# Ethernet.net
KiCad netlist of a schematic drawn in Altium Designer
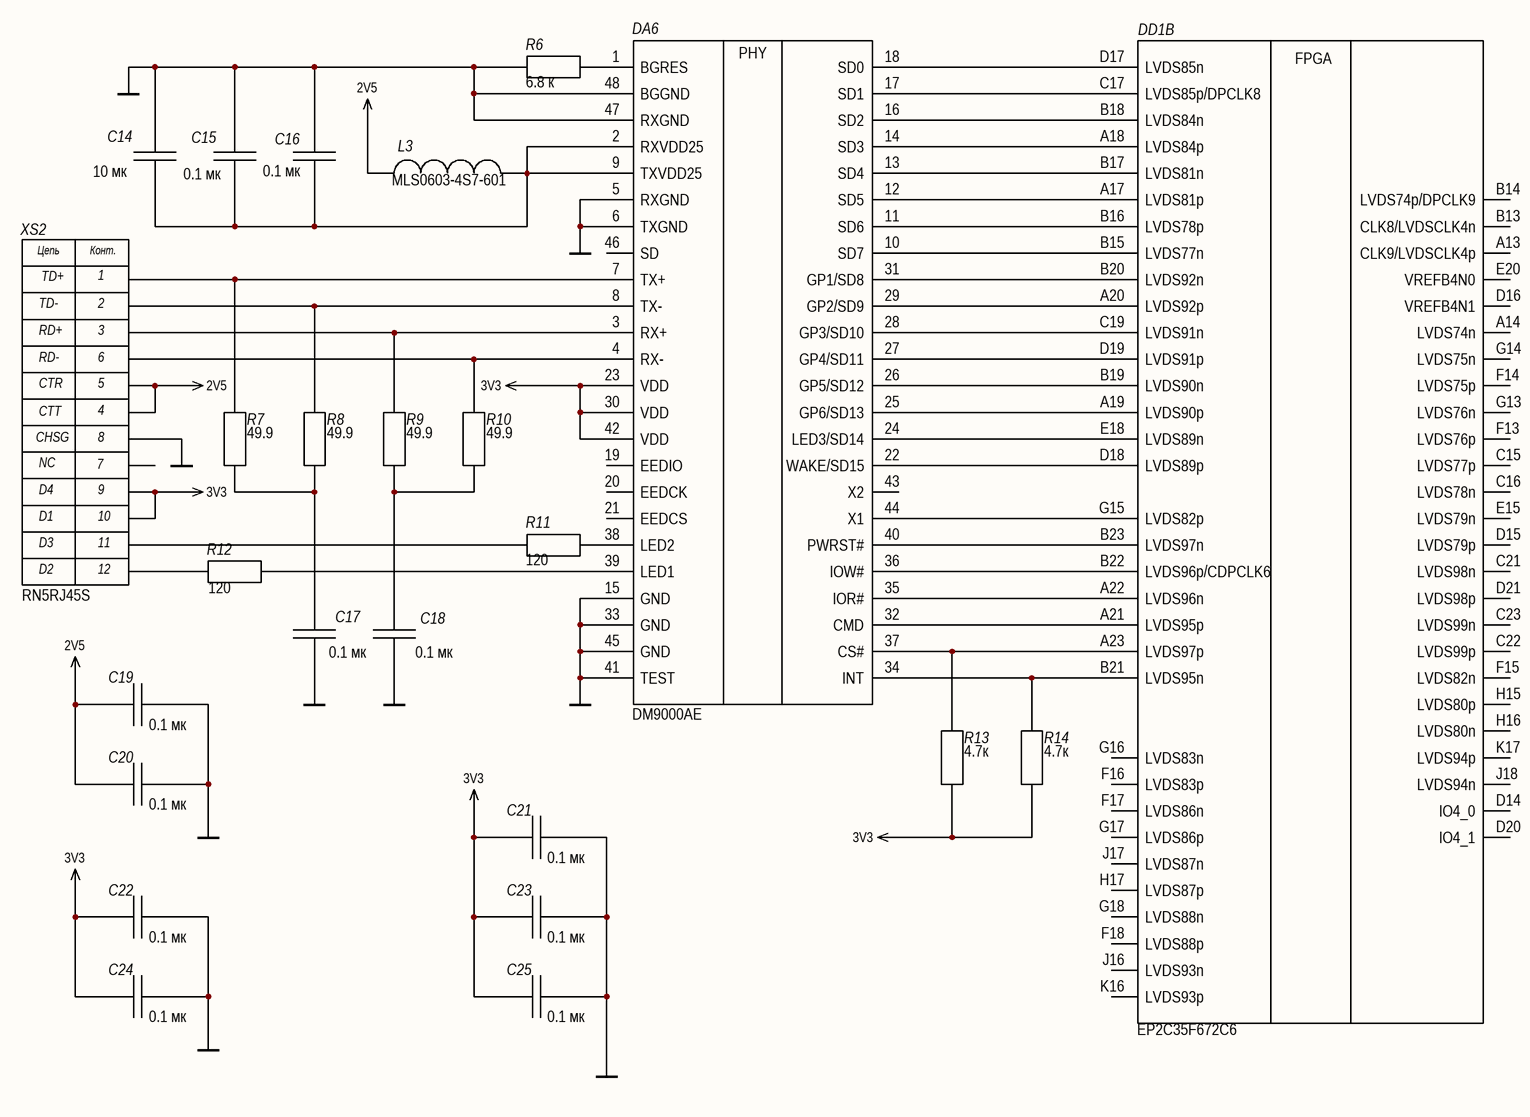
[diagram p0: Ethernet.SchDoc]

(export (version "E")
  (design (tool "Eeschema 10.0.6"))
  (components
    (comp (ref "C14") (value "~") (libsource (lib "Schlib1") (part "C")))
    (comp (ref "C15") (value "~") (libsource (lib "Schlib1") (part "C")))
    (comp (ref "C16") (value "~") (libsource (lib "Schlib1") (part "C")))
    (comp (ref "C17") (value "~") (libsource (lib "Schlib1") (part "C")))
    (comp (ref "C18") (value "~") (libsource (lib "Schlib1") (part "C")))
    (comp (ref "C19") (value "~") (libsource (lib "Schlib1") (part "C")))
    (comp (ref "C20") (value "~") (libsource (lib "Schlib1") (part "C")))
    (comp (ref "C21") (value "~") (libsource (lib "Schlib1") (part "C")))
    (comp (ref "C22") (value "~") (libsource (lib "Schlib1") (part "C")))
    (comp (ref "C23") (value "~") (libsource (lib "Schlib1") (part "C")))
    (comp (ref "C24") (value "~") (libsource (lib "Schlib1") (part "C")))
    (comp (ref "C25") (value "~") (libsource (lib "Schlib1") (part "C")))
    (comp (ref "DA6") (value "DM9000AE") (libsource (lib "Schlib1") (part "DM9000AE")))
    (comp (ref "DD1") (value "EP2C35F672C6") (libsource (lib "Schlib1") (part "PLIS")))
    (comp (ref "L3") (value "L") (libsource (lib "Schlib1") (part "L")))
    (comp (ref "R6") (value "6.8 к") (libsource (lib "Schlib1") (part "R")))
    (comp (ref "R7") (value "49.9") (libsource (lib "Schlib1") (part "R")))
    (comp (ref "R8") (value "49.9") (libsource (lib "Schlib1") (part "R")))
    (comp (ref "R9") (value "49.9") (libsource (lib "Schlib1") (part "R")))
    (comp (ref "R10") (value "49.9") (libsource (lib "Schlib1") (part "R")))
    (comp (ref "R11") (value "120") (libsource (lib "Schlib1") (part "R")))
    (comp (ref "R12") (value "120") (libsource (lib "Schlib1") (part "R")))
    (comp (ref "R13") (value "4.7к") (libsource (lib "Schlib1") (part "R")))
    (comp (ref "R14") (value "4.7к") (libsource (lib "Schlib1") (part "R")))
    (comp (ref "XS2") (value "RN5RJ45S") (libsource (lib "Schlib1") (part "Ethernet_RJ45")))
  )
  (nets
    (net (code "1") (name "2V5") (class "Default")
      (node (ref "C19") (pin "2") (pintype "passive"))
      (node (ref "C20") (pin "2") (pintype "passive"))
      (node (ref "L3") (pin "1") (pinfunction "1_1") (pintype "passive"))
      (node (ref "XS2") (pin "4") (pinfunction "4_4") (pintype "passive"))
      (node (ref "XS2") (pin "5") (pinfunction "5_5") (pintype "passive"))
    )
    (net (code "2") (name "3V3") (class "Default")
      (node (ref "C21") (pin "2") (pintype "passive"))
      (node (ref "C22") (pin "2") (pintype "passive"))
      (node (ref "C23") (pin "2") (pintype "passive"))
      (node (ref "C24") (pin "2") (pintype "passive"))
      (node (ref "C25") (pin "2") (pintype "passive"))
      (node (ref "DA6") (pin "23") (pinfunction "VDD_23") (pintype "passive"))
      (node (ref "DA6") (pin "30") (pinfunction "VDD_30") (pintype "passive"))
      (node (ref "DA6") (pin "42") (pinfunction "VDD_42") (pintype "passive"))
      (node (ref "R13") (pin "1") (pinfunction "1_1") (pintype "passive"))
      (node (ref "R14") (pin "1") (pinfunction "1_1") (pintype "passive"))
      (node (ref "XS2") (pin "10") (pinfunction "10_10") (pintype "passive"))
      (node (ref "XS2") (pin "9") (pinfunction "9_9") (pintype "passive"))
    )
    (net (code "3") (name "GND") (class "Default")
      (node (ref "C14") (pin "2") (pintype "passive"))
      (node (ref "C15") (pin "2") (pintype "passive"))
      (node (ref "C16") (pin "2") (pintype "passive"))
      (node (ref "C17") (pin "1") (pintype "passive"))
      (node (ref "C18") (pin "1") (pintype "passive"))
      (node (ref "C19") (pin "1") (pintype "passive"))
      (node (ref "C20") (pin "1") (pintype "passive"))
      (node (ref "C21") (pin "1") (pintype "passive"))
      (node (ref "C22") (pin "1") (pintype "passive"))
      (node (ref "C23") (pin "1") (pintype "passive"))
      (node (ref "C24") (pin "1") (pintype "passive"))
      (node (ref "C25") (pin "1") (pintype "passive"))
      (node (ref "DA6") (pin "15") (pinfunction "GND_15") (pintype "passive"))
      (node (ref "DA6") (pin "33") (pinfunction "GND_33") (pintype "passive"))
      (node (ref "DA6") (pin "41") (pinfunction "TEST_41") (pintype "passive"))
      (node (ref "DA6") (pin "45") (pinfunction "GND_45") (pintype "passive"))
      (node (ref "DA6") (pin "47") (pinfunction "RXGND_47") (pintype "passive"))
      (node (ref "DA6") (pin "48") (pinfunction "BGGND_48") (pintype "passive"))
      (node (ref "DA6") (pin "5") (pinfunction "RXGND_5") (pintype "passive"))
      (node (ref "DA6") (pin "6") (pinfunction "TXGND_6") (pintype "passive"))
      (node (ref "R6") (pin "1") (pinfunction "1_1") (pintype "passive"))
      (node (ref "XS2") (pin "8") (pinfunction "8_8") (pintype "passive"))
    )
    (net (code "4") (name "Net-(C17-Pad2)") (class "Default")
      (node (ref "C17") (pin "2") (pintype "passive"))
      (node (ref "R7") (pin "1") (pinfunction "1_1") (pintype "passive"))
      (node (ref "R8") (pin "1") (pinfunction "1_1") (pintype "passive"))
    )
    (net (code "5") (name "Net-(C18-Pad2)") (class "Default")
      (node (ref "C18") (pin "2") (pintype "passive"))
      (node (ref "R10") (pin "1") (pinfunction "1_1") (pintype "passive"))
      (node (ref "R9") (pin "1") (pinfunction "1_1") (pintype "passive"))
    )
    (net (code "6") (name "Net-(DA6-BGRES)") (class "Default")
      (node (ref "DA6") (pin "1") (pinfunction "BGRES_1") (pintype "passive"))
      (node (ref "R6") (pin "2") (pinfunction "2_2") (pintype "passive"))
    )
    (net (code "7") (name "Net-(DA6-CMD)") (class "Default")
      (node (ref "DA6") (pin "32") (pinfunction "CMD_32") (pintype "passive"))
      (node (ref "DD1") (pin "A21") (pinfunction "LVDS95p_A21") (pintype "passive"))
    )
    (net (code "8") (name "Net-(DA6-CS#)") (class "Default")
      (node (ref "DA6") (pin "37") (pinfunction "CS#_37") (pintype "passive"))
      (node (ref "DD1") (pin "A23") (pinfunction "LVDS97p_A23") (pintype "passive"))
      (node (ref "R13") (pin "2") (pinfunction "2_2") (pintype "passive"))
    )
    (net (code "9") (name "Net-(DA6-GP1{slash}SD8)") (class "Default")
      (node (ref "DA6") (pin "31") (pinfunction "GP1/SD8_31") (pintype "passive"))
      (node (ref "DD1") (pin "B20") (pinfunction "LVDS92n_B20") (pintype "passive"))
    )
    (net (code "10") (name "Net-(DA6-GP2{slash}SD9)") (class "Default")
      (node (ref "DA6") (pin "29") (pinfunction "GP2/SD9_29") (pintype "passive"))
      (node (ref "DD1") (pin "A20") (pinfunction "LVDS92p_A20") (pintype "passive"))
    )
    (net (code "11") (name "Net-(DA6-GP3{slash}SD10)") (class "Default")
      (node (ref "DA6") (pin "28") (pinfunction "GP3/SD10_28") (pintype "passive"))
      (node (ref "DD1") (pin "C19") (pinfunction "LVDS91n_C19") (pintype "passive"))
    )
    (net (code "12") (name "Net-(DA6-GP4{slash}SD11)") (class "Default")
      (node (ref "DA6") (pin "27") (pinfunction "GP4/SD11_27") (pintype "passive"))
      (node (ref "DD1") (pin "D19") (pinfunction "LVDS91p_D19") (pintype "passive"))
    )
    (net (code "13") (name "Net-(DA6-GP5{slash}SD12)") (class "Default")
      (node (ref "DA6") (pin "26") (pinfunction "GP5/SD12_26") (pintype "passive"))
      (node (ref "DD1") (pin "B19") (pinfunction "LVDS90n_B19") (pintype "passive"))
    )
    (net (code "14") (name "Net-(DA6-GP6{slash}SD13)") (class "Default")
      (node (ref "DA6") (pin "25") (pinfunction "GP6/SD13_25") (pintype "passive"))
      (node (ref "DD1") (pin "A19") (pinfunction "LVDS90p_A19") (pintype "passive"))
    )
    (net (code "15") (name "Net-(DA6-INT)") (class "Default")
      (node (ref "DA6") (pin "34") (pinfunction "INT_34") (pintype "passive"))
      (node (ref "DD1") (pin "B21") (pinfunction "LVDS95n_B21") (pintype "passive"))
      (node (ref "R14") (pin "2") (pinfunction "2_2") (pintype "passive"))
    )
    (net (code "16") (name "Net-(DA6-IOR#)") (class "Default")
      (node (ref "DA6") (pin "35") (pinfunction "IOR#_35") (pintype "passive"))
      (node (ref "DD1") (pin "A22") (pinfunction "LVDS96n_A22") (pintype "passive"))
    )
    (net (code "17") (name "Net-(DA6-IOW#)") (class "Default")
      (node (ref "DA6") (pin "36") (pinfunction "IOW#_36") (pintype "passive"))
      (node (ref "DD1") (pin "B22") (pinfunction "LVDS96p/CDPCLK6_B22") (pintype "passive"))
    )
    (net (code "18") (name "Net-(DA6-LED1)") (class "Default")
      (node (ref "DA6") (pin "39") (pinfunction "LED1_39") (pintype "passive"))
      (node (ref "R12") (pin "2") (pinfunction "2_2") (pintype "passive"))
    )
    (net (code "19") (name "Net-(DA6-LED2)") (class "Default")
      (node (ref "DA6") (pin "38") (pinfunction "LED2_38") (pintype "passive"))
      (node (ref "R11") (pin "2") (pinfunction "2_2") (pintype "passive"))
    )
    (net (code "20") (name "Net-(DA6-LED3{slash}SD14)") (class "Default")
      (node (ref "DA6") (pin "24") (pinfunction "LED3/SD14_24") (pintype "passive"))
      (node (ref "DD1") (pin "E18") (pinfunction "LVDS89n_E18") (pintype "passive"))
    )
    (net (code "21") (name "Net-(DA6-PWRST#)") (class "Default")
      (node (ref "DA6") (pin "40") (pinfunction "PWRST#_40") (pintype "passive"))
      (node (ref "DD1") (pin "B23") (pinfunction "LVDS97n_B23") (pintype "passive"))
    )
    (net (code "22") (name "Net-(DA6-RX+)") (class "Default")
      (node (ref "DA6") (pin "3") (pinfunction "RX+_3") (pintype "passive"))
      (node (ref "R9") (pin "2") (pinfunction "2_2") (pintype "passive"))
      (node (ref "XS2") (pin "3") (pinfunction "3_3") (pintype "passive"))
    )
    (net (code "23") (name "Net-(DA6-RX-)") (class "Default")
      (node (ref "DA6") (pin "4") (pinfunction "RX-_4") (pintype "passive"))
      (node (ref "R10") (pin "2") (pinfunction "2_2") (pintype "passive"))
      (node (ref "XS2") (pin "6") (pinfunction "6_6") (pintype "passive"))
    )
    (net (code "24") (name "Net-(DA6-RXVDD25)") (class "Default")
      (node (ref "C14") (pin "1") (pintype "passive"))
      (node (ref "C15") (pin "1") (pintype "passive"))
      (node (ref "C16") (pin "1") (pintype "passive"))
      (node (ref "DA6") (pin "2") (pinfunction "RXVDD25_2") (pintype "passive"))
      (node (ref "DA6") (pin "9") (pinfunction "TXVDD25_9") (pintype "passive"))
      (node (ref "L3") (pin "2") (pinfunction "2_2") (pintype "passive"))
    )
    (net (code "25") (name "Net-(DA6-SD0)") (class "Default")
      (node (ref "DA6") (pin "18") (pinfunction "SD0_18") (pintype "passive"))
      (node (ref "DD1") (pin "D17") (pinfunction "LVDS85n_D17") (pintype "passive"))
    )
    (net (code "26") (name "Net-(DA6-SD1)") (class "Default")
      (node (ref "DA6") (pin "17") (pinfunction "SD1_17") (pintype "passive"))
      (node (ref "DD1") (pin "C17") (pinfunction "LVDS85p/DPCLK8_C17") (pintype "passive"))
    )
    (net (code "27") (name "Net-(DA6-SD2)") (class "Default")
      (node (ref "DA6") (pin "16") (pinfunction "SD2_16") (pintype "passive"))
      (node (ref "DD1") (pin "B18") (pinfunction "LVDS84n_B18") (pintype "passive"))
    )
    (net (code "28") (name "Net-(DA6-SD3)") (class "Default")
      (node (ref "DA6") (pin "14") (pinfunction "SD3_14") (pintype "passive"))
      (node (ref "DD1") (pin "A18") (pinfunction "LVDS84p_A18") (pintype "passive"))
    )
    (net (code "29") (name "Net-(DA6-SD4)") (class "Default")
      (node (ref "DA6") (pin "13") (pinfunction "SD4_13") (pintype "passive"))
      (node (ref "DD1") (pin "B17") (pinfunction "LVDS81n_B17") (pintype "passive"))
    )
    (net (code "30") (name "Net-(DA6-SD5)") (class "Default")
      (node (ref "DA6") (pin "12") (pinfunction "SD5_12") (pintype "passive"))
      (node (ref "DD1") (pin "A17") (pinfunction "LVDS81p_A17") (pintype "passive"))
    )
    (net (code "31") (name "Net-(DA6-SD6)") (class "Default")
      (node (ref "DA6") (pin "11") (pinfunction "SD6_11") (pintype "passive"))
      (node (ref "DD1") (pin "B16") (pinfunction "LVDS78p_B16") (pintype "passive"))
    )
    (net (code "32") (name "Net-(DA6-SD7)") (class "Default")
      (node (ref "DA6") (pin "10") (pinfunction "SD7_10") (pintype "passive"))
      (node (ref "DD1") (pin "B15") (pinfunction "LVDS77n_B15") (pintype "passive"))
    )
    (net (code "33") (name "Net-(DA6-TX+)") (class "Default")
      (node (ref "DA6") (pin "7") (pinfunction "TX+_7") (pintype "passive"))
      (node (ref "R7") (pin "2") (pinfunction "2_2") (pintype "passive"))
      (node (ref "XS2") (pin "1") (pinfunction "1_1") (pintype "passive"))
    )
    (net (code "34") (name "Net-(DA6-TX-)") (class "Default")
      (node (ref "DA6") (pin "8") (pinfunction "TX-_8") (pintype "passive"))
      (node (ref "R8") (pin "2") (pinfunction "2_2") (pintype "passive"))
      (node (ref "XS2") (pin "2") (pinfunction "2_2") (pintype "passive"))
    )
    (net (code "35") (name "Net-(DA6-WAKE{slash}SD15)") (class "Default")
      (node (ref "DA6") (pin "22") (pinfunction "WAKE/SD15_22") (pintype "passive"))
      (node (ref "DD1") (pin "D18") (pinfunction "LVDS89p_D18") (pintype "passive"))
    )
    (net (code "36") (name "Net-(DA6-X1)") (class "Default")
      (node (ref "DA6") (pin "44") (pinfunction "X1_44") (pintype "passive"))
      (node (ref "DD1") (pin "G15") (pinfunction "LVDS82p_G15") (pintype "passive"))
    )
    (net (code "37") (name "Net-(R11-Pad1)") (class "Default")
      (node (ref "R11") (pin "1") (pinfunction "1_1") (pintype "passive"))
      (node (ref "XS2") (pin "11") (pinfunction "11_11") (pintype "passive"))
    )
    (net (code "38") (name "Net-(R12-Pad1)") (class "Default")
      (node (ref "R12") (pin "1") (pinfunction "1_1") (pintype "passive"))
      (node (ref "XS2") (pin "12") (pinfunction "12_12") (pintype "passive"))
    )
    (net (code "39") (name "unconnected-(DA6-EEDCK-Pad20)") (class "Default")
      (node (ref "DA6") (pin "20") (pinfunction "EEDCK_20") (pintype "passive"))
    )
    (net (code "40") (name "unconnected-(DA6-EEDCS-Pad21)") (class "Default")
      (node (ref "DA6") (pin "21") (pinfunction "EEDCS_21") (pintype "passive"))
    )
    (net (code "41") (name "unconnected-(DA6-EEDIO-Pad19)") (class "Default")
      (node (ref "DA6") (pin "19") (pinfunction "EEDIO_19") (pintype "passive"))
    )
    (net (code "42") (name "unconnected-(DA6-SD-Pad46)") (class "Default")
      (node (ref "DA6") (pin "46") (pinfunction "SD_46") (pintype "passive"))
    )
    (net (code "43") (name "unconnected-(DA6-X2-Pad43)") (class "Default")
      (node (ref "DA6") (pin "43") (pinfunction "X2_43") (pintype "passive"))
    )
    (net (code "44") (name "unconnected-(DD1B-CLK8{slash}LVDSCLK4n-PadB13)") (class "Default")
      (node (ref "DD1") (pin "B13") (pinfunction "CLK8/LVDSCLK4n_B13") (pintype "passive"))
    )
    (net (code "45") (name "unconnected-(DD1B-CLK9{slash}LVDSCLK4p-PadA13)") (class "Default")
      (node (ref "DD1") (pin "A13") (pinfunction "CLK9/LVDSCLK4p_A13") (pintype "passive"))
    )
    (net (code "46") (name "unconnected-(DD1B-IO4_0-PadD14)") (class "Default")
      (node (ref "DD1") (pin "D14") (pinfunction "IO4_0_D14") (pintype "passive"))
    )
    (net (code "47") (name "unconnected-(DD1B-IO4_1-PadD20)") (class "Default")
      (node (ref "DD1") (pin "D20") (pinfunction "IO4_1_D20") (pintype "passive"))
    )
    (net (code "48") (name "unconnected-(DD1B-LVDS74n-PadA14)") (class "Default")
      (node (ref "DD1") (pin "A14") (pinfunction "LVDS74n_A14") (pintype "passive"))
    )
    (net (code "49") (name "unconnected-(DD1B-LVDS74p{slash}DPCLK9-PadB14)") (class "Default")
      (node (ref "DD1") (pin "B14") (pinfunction "LVDS74p/DPCLK9_B14") (pintype "passive"))
    )
    (net (code "50") (name "unconnected-(DD1B-LVDS75n-PadG14)") (class "Default")
      (node (ref "DD1") (pin "G14") (pinfunction "LVDS75n_G14") (pintype "passive"))
    )
    (net (code "51") (name "unconnected-(DD1B-LVDS75p-PadF14)") (class "Default")
      (node (ref "DD1") (pin "F14") (pinfunction "LVDS75p_F14") (pintype "passive"))
    )
    (net (code "52") (name "unconnected-(DD1B-LVDS76n-PadG13)") (class "Default")
      (node (ref "DD1") (pin "G13") (pinfunction "LVDS76n_G13") (pintype "passive"))
    )
    (net (code "53") (name "unconnected-(DD1B-LVDS76p-PadF13)") (class "Default")
      (node (ref "DD1") (pin "F13") (pinfunction "LVDS76p_F13") (pintype "passive"))
    )
    (net (code "54") (name "unconnected-(DD1B-LVDS77p-PadC15)") (class "Default")
      (node (ref "DD1") (pin "C15") (pinfunction "LVDS77p_C15") (pintype "passive"))
    )
    (net (code "55") (name "unconnected-(DD1B-LVDS78n-PadC16)") (class "Default")
      (node (ref "DD1") (pin "C16") (pinfunction "LVDS78n_C16") (pintype "passive"))
    )
    (net (code "56") (name "unconnected-(DD1B-LVDS79n-PadE15)") (class "Default")
      (node (ref "DD1") (pin "E15") (pinfunction "LVDS79n_E15") (pintype "passive"))
    )
    (net (code "57") (name "unconnected-(DD1B-LVDS79p-PadD15)") (class "Default")
      (node (ref "DD1") (pin "D15") (pinfunction "LVDS79p_D15") (pintype "passive"))
    )
    (net (code "58") (name "unconnected-(DD1B-LVDS80n-PadH16)") (class "Default")
      (node (ref "DD1") (pin "H16") (pinfunction "LVDS80n_H16") (pintype "passive"))
    )
    (net (code "59") (name "unconnected-(DD1B-LVDS80p-PadH15)") (class "Default")
      (node (ref "DD1") (pin "H15") (pinfunction "LVDS80p_H15") (pintype "passive"))
    )
    (net (code "60") (name "unconnected-(DD1B-LVDS82n-PadF15)") (class "Default")
      (node (ref "DD1") (pin "F15") (pinfunction "LVDS82n_F15") (pintype "passive"))
    )
    (net (code "61") (name "unconnected-(DD1B-LVDS83n-PadG16)") (class "Default")
      (node (ref "DD1") (pin "G16") (pinfunction "LVDS83n_G16") (pintype "passive"))
    )
    (net (code "62") (name "unconnected-(DD1B-LVDS83p-PadF16)") (class "Default")
      (node (ref "DD1") (pin "F16") (pinfunction "LVDS83p_F16") (pintype "passive"))
    )
    (net (code "63") (name "unconnected-(DD1B-LVDS86n-PadF17)") (class "Default")
      (node (ref "DD1") (pin "F17") (pinfunction "LVDS86n_F17") (pintype "passive"))
    )
    (net (code "64") (name "unconnected-(DD1B-LVDS86p-PadG17)") (class "Default")
      (node (ref "DD1") (pin "G17") (pinfunction "LVDS86p_G17") (pintype "passive"))
    )
    (net (code "65") (name "unconnected-(DD1B-LVDS87n-PadJ17)") (class "Default")
      (node (ref "DD1") (pin "J17") (pinfunction "LVDS87n_J17") (pintype "passive"))
    )
    (net (code "66") (name "unconnected-(DD1B-LVDS87p-PadH17)") (class "Default")
      (node (ref "DD1") (pin "H17") (pinfunction "LVDS87p_H17") (pintype "passive"))
    )
    (net (code "67") (name "unconnected-(DD1B-LVDS88n-PadG18)") (class "Default")
      (node (ref "DD1") (pin "G18") (pinfunction "LVDS88n_G18") (pintype "passive"))
    )
    (net (code "68") (name "unconnected-(DD1B-LVDS88p-PadF18)") (class "Default")
      (node (ref "DD1") (pin "F18") (pinfunction "LVDS88p_F18") (pintype "passive"))
    )
    (net (code "69") (name "unconnected-(DD1B-LVDS93n-PadJ16)") (class "Default")
      (node (ref "DD1") (pin "J16") (pinfunction "LVDS93n_J16") (pintype "passive"))
    )
    (net (code "70") (name "unconnected-(DD1B-LVDS93p-PadK16)") (class "Default")
      (node (ref "DD1") (pin "K16") (pinfunction "LVDS93p_K16") (pintype "passive"))
    )
    (net (code "71") (name "unconnected-(DD1B-LVDS94n-PadJ18)") (class "Default")
      (node (ref "DD1") (pin "J18") (pinfunction "LVDS94n_J18") (pintype "passive"))
    )
    (net (code "72") (name "unconnected-(DD1B-LVDS94p-PadK17)") (class "Default")
      (node (ref "DD1") (pin "K17") (pinfunction "LVDS94p_K17") (pintype "passive"))
    )
    (net (code "73") (name "unconnected-(DD1B-LVDS98n-PadC21)") (class "Default")
      (node (ref "DD1") (pin "C21") (pinfunction "LVDS98n_C21") (pintype "passive"))
    )
    (net (code "74") (name "unconnected-(DD1B-LVDS98p-PadD21)") (class "Default")
      (node (ref "DD1") (pin "D21") (pinfunction "LVDS98p_D21") (pintype "passive"))
    )
    (net (code "75") (name "unconnected-(DD1B-LVDS99n-PadC23)") (class "Default")
      (node (ref "DD1") (pin "C23") (pinfunction "LVDS99n_C23") (pintype "passive"))
    )
    (net (code "76") (name "unconnected-(DD1B-LVDS99p-PadC22)") (class "Default")
      (node (ref "DD1") (pin "C22") (pinfunction "LVDS99p_C22") (pintype "passive"))
    )
    (net (code "77") (name "unconnected-(DD1B-VREFB4N0-PadE20)") (class "Default")
      (node (ref "DD1") (pin "E20") (pinfunction "VREFB4N0_E20") (pintype "passive"))
    )
    (net (code "78") (name "unconnected-(DD1B-VREFB4N1-PadD16)") (class "Default")
      (node (ref "DD1") (pin "D16") (pinfunction "VREFB4N1_D16") (pintype "passive"))
    )
    (net (code "79") (name "unconnected-(XS2-Pad7)") (class "Default")
      (node (ref "XS2") (pin "7") (pinfunction "7_7") (pintype "passive"))
    )
  )
)
